# ProPrj_OpenTCUV4_2026-04-02.net
KiCad netlist of a schematic drawn in EasyEDA Pro
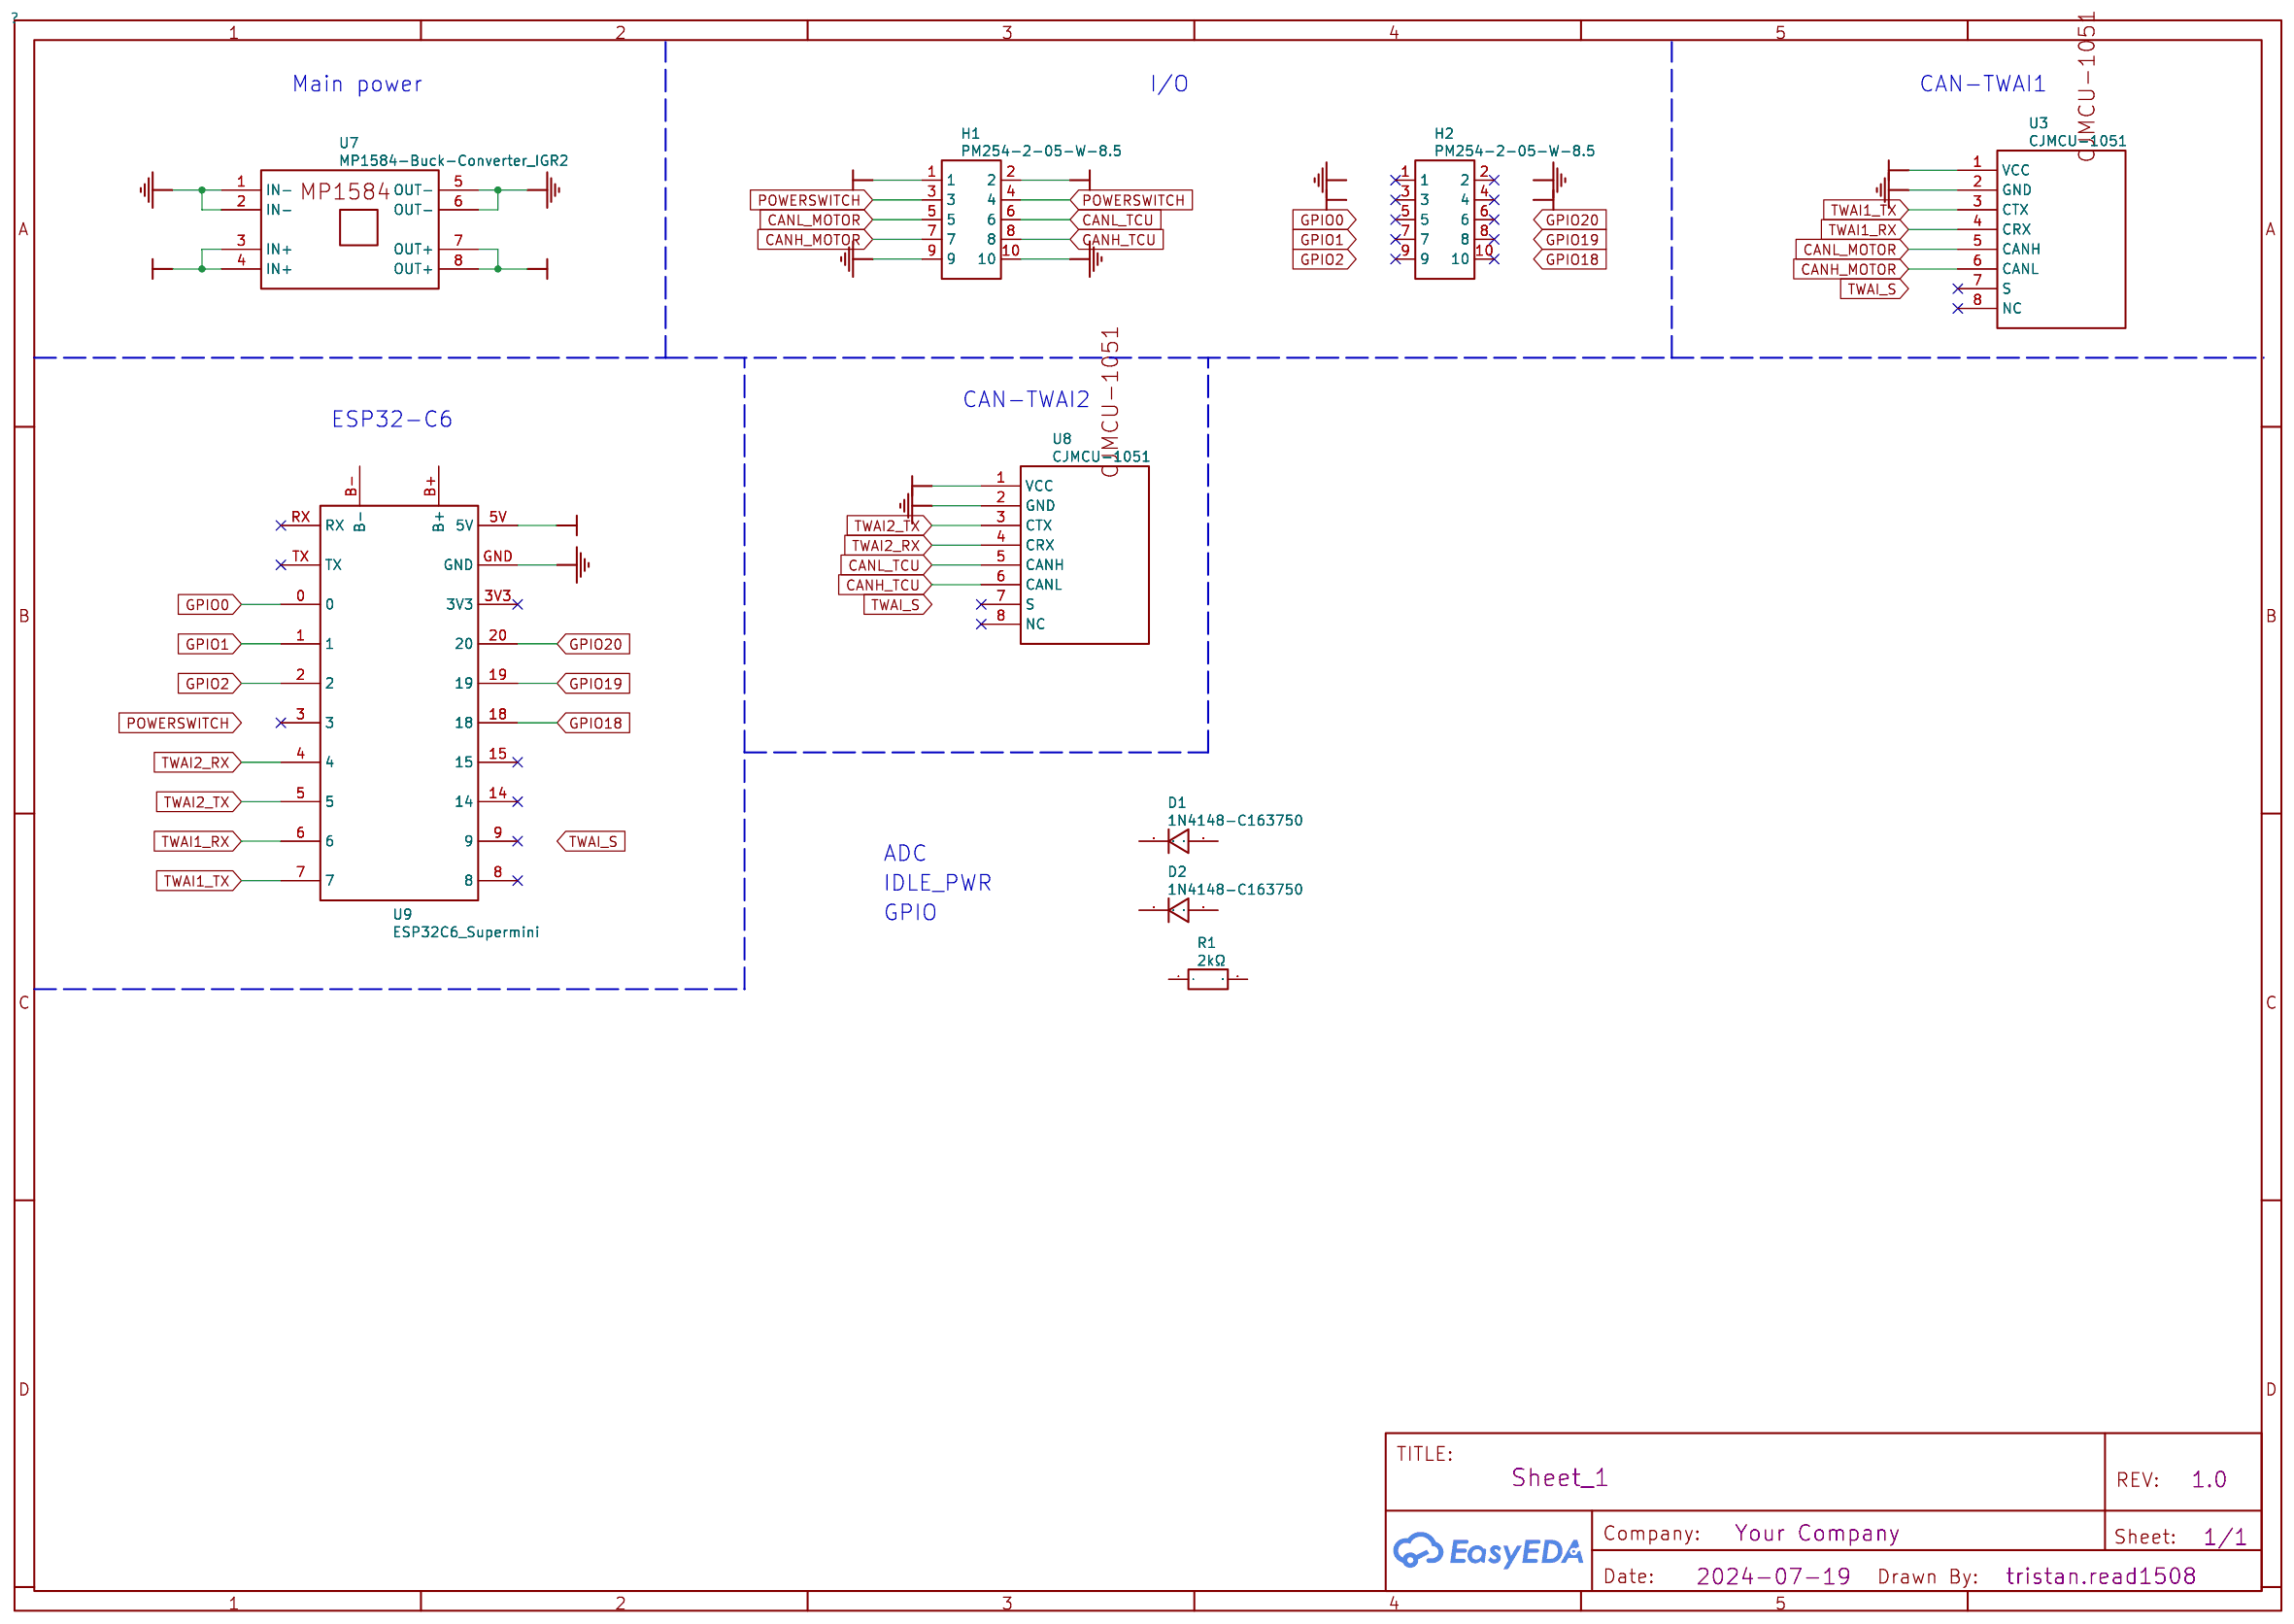
[diagram p0: schematic sheet]

(export (version "E")
  (design (tool "Eeschema 10.0.6"))
  (components
    (comp (ref "D1")
      (value "1N4148-C163750")
      (footprint "easyedapro:DO-35_BD2.0-L4.2-P8.20-D0.5-RD")
      (fields
        (field (name "Manufacturer Part") "1N4148")
        (field (name "Manufacturer") "FMS(美丽微)")
        (field (name "Contributor") "LCSC")
      )
      (libsource (lib "easyedapro") (part "1N4148-C163750"))
    )
    (comp (ref "D2")
      (value "1N4148-C163750")
      (footprint "easyedapro:DO-35_BD2.0-L4.2-P8.20-D0.5-RD")
      (fields
        (field (name "Manufacturer Part") "1N4148")
        (field (name "Manufacturer") "FMS(美丽微)")
        (field (name "Contributor") "LCSC")
      )
      (libsource (lib "easyedapro") (part "1N4148-C163750"))
    )
    (comp (ref "H1")
      (value "PM254-2-05-W-8.5")
      (footprint "easyedapro:HDR-TH_10P-P2.54-H-F-R2-C5-W8.5")
      (fields (field (name "Manufacturer") "HCTL(华灿天禄)") (field (name "Contributor") "LCSC"))
      (libsource (lib "easyedapro") (part "PM254-2-05-W-8.5"))
    )
    (comp (ref "H2")
      (value "PM254-2-05-W-8.5")
      (footprint "easyedapro:HDR-TH_10P-P2.54-H-F-R2-C5-W8.5")
      (fields (field (name "Manufacturer") "HCTL(华灿天禄)") (field (name "Contributor") "LCSC"))
      (libsource (lib "easyedapro") (part "PM254-2-05-W-8.5"))
    )
    (comp (ref "R1")
      (value "2kΩ")
      (footprint "easyedapro:RES-TH_BD2.4-L6.3-P10.30-D0.6")
      (fields
        (field (name "Manufacturer Part") "RN1/4W2KFT/BA1")
        (field (name "Manufacturer") "Tyohm(幸亚电阻)")
        (field (name "Contributor") "LCSC")
      )
      (libsource (lib "easyedapro") (part "2kΩ"))
    )
    (comp (ref "U3")
      (value "CJMCU-1051")
      (footprint "easyedapro:CJMCU-1051")
      (fields (field (name "Contributor") "ratedspg10"))
      (libsource (lib "easyedapro") (part "CJMCU-1051"))
    )
    (comp (ref "U7")
      (value "MP1584-Buck-Converter_IGR2")
      (footprint "easyedapro:MP1584EN-BUCK-CONVERTER")
      (fields (field (name "Manufacturer Part") "MP1584EN") (field (name "Contributor") "fazli wadood"))
      (libsource (lib "easyedapro") (part "MP1584-Buck-Converter_IGR2"))
    )
    (comp (ref "U8")
      (value "CJMCU-1051")
      (footprint "easyedapro:CJMCU-1051")
      (fields (field (name "Contributor") "ratedspg10"))
      (libsource (lib "easyedapro") (part "CJMCU-1051"))
    )
    (comp (ref "U9")
      (value "ESP32C6_Supermini")
      (footprint "easyedapro:ESP32-C6-SUPERMINI")
      (fields (field (name "Contributor") "Guest"))
      (libsource (lib "easyedapro") (part "ESP32C6_Supermini"))
    )
  )
  (nets
    (net (code "1") (name "+5V") (class "Default")
      (node (ref "U3") (pin "1") (pinfunction "VCC_1") (pintype "unspecified"))
      (node (ref "U7") (pin "7") (pinfunction "OUT+_7") (pintype "unspecified"))
      (node (ref "U7") (pin "8") (pinfunction "OUT+_8") (pintype "unspecified"))
      (node (ref "U8") (pin "1") (pinfunction "VCC_1") (pintype "unspecified"))
      (node (ref "U9") (pin "5V") (pinfunction "5V_5V") (pintype "unspecified"))
    )
    (net (code "2") (name "CANH_MOTOR") (class "Default")
      (node (ref "H1") (pin "7") (pinfunction "7_7") (pintype "unspecified"))
      (node (ref "U3") (pin "6") (pinfunction "CANL_6") (pintype "unspecified"))
    )
    (net (code "3") (name "CANH_TCU") (class "Default")
      (node (ref "H1") (pin "8") (pinfunction "8_8") (pintype "unspecified"))
      (node (ref "U8") (pin "6") (pinfunction "CANL_6") (pintype "unspecified"))
    )
    (net (code "4") (name "CANL_MOTOR") (class "Default")
      (node (ref "H1") (pin "5") (pinfunction "5_5") (pintype "unspecified"))
      (node (ref "U3") (pin "5") (pinfunction "CANH_5") (pintype "unspecified"))
    )
    (net (code "5") (name "CANL_TCU") (class "Default")
      (node (ref "H1") (pin "6") (pinfunction "6_6") (pintype "unspecified"))
      (node (ref "U8") (pin "5") (pinfunction "CANH_5") (pintype "unspecified"))
    )
    (net (code "6") (name "GND") (class "Default")
      (node (ref "H1") (pin "10") (pinfunction "10_10") (pintype "unspecified"))
      (node (ref "H1") (pin "9") (pinfunction "9_9") (pintype "unspecified"))
      (node (ref "U3") (pin "2") (pinfunction "GND_2") (pintype "unspecified"))
      (node (ref "U7") (pin "1") (pinfunction "IN-_1") (pintype "unspecified"))
      (node (ref "U7") (pin "2") (pinfunction "IN-_2") (pintype "unspecified"))
      (node (ref "U7") (pin "5") (pinfunction "OUT-_5") (pintype "unspecified"))
      (node (ref "U7") (pin "6") (pinfunction "OUT-_6") (pintype "unspecified"))
      (node (ref "U8") (pin "2") (pinfunction "GND_2") (pintype "unspecified"))
      (node (ref "U9") (pin "GND") (pinfunction "GND_GND") (pintype "unspecified"))
    )
    (net (code "7") (name "GPIO0") (class "Default")
      (node (ref "U9") (pin "0") (pinfunction "0_0") (pintype "bidirectional"))
    )
    (net (code "8") (name "GPIO1") (class "Default")
      (node (ref "U9") (pin "1") (pinfunction "1_1") (pintype "bidirectional"))
    )
    (net (code "9") (name "GPIO2") (class "Default")
      (node (ref "U9") (pin "2") (pinfunction "2_2") (pintype "bidirectional"))
    )
    (net (code "10") (name "GPIO18") (class "Default")
      (node (ref "U9") (pin "18") (pinfunction "18_18") (pintype "unspecified"))
    )
    (net (code "11") (name "GPIO19") (class "Default")
      (node (ref "U9") (pin "19") (pinfunction "19_19") (pintype "unspecified"))
    )
    (net (code "12") (name "GPIO20") (class "Default")
      (node (ref "U9") (pin "20") (pinfunction "20_20") (pintype "unspecified"))
    )
    (net (code "13") (name "POWERSWITCH") (class "Default")
      (node (ref "H1") (pin "3") (pinfunction "3_3") (pintype "unspecified"))
      (node (ref "H1") (pin "4") (pinfunction "4_4") (pintype "unspecified"))
    )
    (net (code "14") (name "TWAI1_RX") (class "Default")
      (node (ref "U3") (pin "4") (pinfunction "CRX_4") (pintype "unspecified"))
      (node (ref "U9") (pin "6") (pinfunction "6_6") (pintype "bidirectional"))
    )
    (net (code "15") (name "TWAI1_TX") (class "Default")
      (node (ref "U3") (pin "3") (pinfunction "CTX_3") (pintype "unspecified"))
      (node (ref "U9") (pin "7") (pinfunction "7_7") (pintype "bidirectional"))
    )
    (net (code "16") (name "TWAI2_RX") (class "Default")
      (node (ref "U8") (pin "4") (pinfunction "CRX_4") (pintype "unspecified"))
      (node (ref "U9") (pin "4") (pinfunction "4_4") (pintype "bidirectional"))
    )
    (net (code "17") (name "TWAI2_TX") (class "Default")
      (node (ref "U8") (pin "3") (pinfunction "CTX_3") (pintype "unspecified"))
      (node (ref "U9") (pin "5") (pinfunction "5_5") (pintype "bidirectional"))
    )
    (net (code "19") (name "VCC") (class "Default")
      (node (ref "H1") (pin "1") (pinfunction "1_1") (pintype "unspecified"))
      (node (ref "H1") (pin "2") (pinfunction "2_2") (pintype "unspecified"))
      (node (ref "U7") (pin "3") (pinfunction "IN+_3") (pintype "unspecified"))
      (node (ref "U7") (pin "4") (pinfunction "IN+_4") (pintype "unspecified"))
    )
    (net (code "20") (name "unconnected-(D1-Pad1)") (class "Default")
      (node (ref "D1") (pin "1") (pinfunction "1_1") (pintype "unspecified"))
    )
    (net (code "21") (name "unconnected-(D1-Pad2)") (class "Default")
      (node (ref "D1") (pin "2") (pinfunction "2_2") (pintype "unspecified"))
    )
    (net (code "22") (name "unconnected-(D2-Pad1)") (class "Default")
      (node (ref "D2") (pin "1") (pinfunction "1_1") (pintype "unspecified"))
    )
    (net (code "23") (name "unconnected-(D2-Pad2)") (class "Default")
      (node (ref "D2") (pin "2") (pinfunction "2_2") (pintype "unspecified"))
    )
    (net (code "24") (name "unconnected-(H2-Pad1)") (class "Default")
      (node (ref "H2") (pin "1") (pinfunction "1_1") (pintype "unspecified+no_connect"))
    )
    (net (code "25") (name "unconnected-(H2-Pad2)") (class "Default")
      (node (ref "H2") (pin "2") (pinfunction "2_2") (pintype "unspecified+no_connect"))
    )
    (net (code "26") (name "unconnected-(H2-Pad3)") (class "Default")
      (node (ref "H2") (pin "3") (pinfunction "3_3") (pintype "unspecified+no_connect"))
    )
    (net (code "27") (name "unconnected-(H2-Pad4)") (class "Default")
      (node (ref "H2") (pin "4") (pinfunction "4_4") (pintype "unspecified+no_connect"))
    )
    (net (code "28") (name "unconnected-(H2-Pad5)") (class "Default")
      (node (ref "H2") (pin "5") (pinfunction "5_5") (pintype "unspecified+no_connect"))
    )
    (net (code "29") (name "unconnected-(H2-Pad6)") (class "Default")
      (node (ref "H2") (pin "6") (pinfunction "6_6") (pintype "unspecified+no_connect"))
    )
    (net (code "30") (name "unconnected-(H2-Pad7)") (class "Default")
      (node (ref "H2") (pin "7") (pinfunction "7_7") (pintype "unspecified+no_connect"))
    )
    (net (code "31") (name "unconnected-(H2-Pad8)") (class "Default")
      (node (ref "H2") (pin "8") (pinfunction "8_8") (pintype "unspecified+no_connect"))
    )
    (net (code "32") (name "unconnected-(H2-Pad9)") (class "Default")
      (node (ref "H2") (pin "9") (pinfunction "9_9") (pintype "unspecified+no_connect"))
    )
    (net (code "33") (name "unconnected-(H2-Pad10)") (class "Default")
      (node (ref "H2") (pin "10") (pinfunction "10_10") (pintype "unspecified+no_connect"))
    )
    (net (code "34") (name "unconnected-(R1-Pad1)") (class "Default")
      (node (ref "R1") (pin "1") (pinfunction "1_1") (pintype "unspecified"))
    )
    (net (code "35") (name "unconnected-(R1-Pad2)") (class "Default")
      (node (ref "R1") (pin "2") (pinfunction "2_2") (pintype "unspecified"))
    )
    (net (code "36") (name "unconnected-(U3-NC-Pad8)") (class "Default")
      (node (ref "U3") (pin "8") (pinfunction "NC_8") (pintype "unspecified+no_connect"))
    )
    (net (code "37") (name "unconnected-(U3-S-Pad7)") (class "Default")
      (node (ref "U3") (pin "7") (pinfunction "S_7") (pintype "unspecified+no_connect"))
    )
    (net (code "38") (name "unconnected-(U8-NC-Pad8)") (class "Default")
      (node (ref "U8") (pin "8") (pinfunction "NC_8") (pintype "unspecified+no_connect"))
    )
    (net (code "39") (name "unconnected-(U8-S-Pad7)") (class "Default")
      (node (ref "U8") (pin "7") (pinfunction "S_7") (pintype "unspecified+no_connect"))
    )
    (net (code "40") (name "unconnected-(U9-Pad3)") (class "Default")
      (node (ref "U9") (pin "3") (pinfunction "3_3") (pintype "bidirectional+no_connect"))
    )
    (net (code "41") (name "unconnected-(U9-Pad3V3)") (class "Default")
      (node (ref "U9") (pin "3V3") (pinfunction "3V3_3V3") (pintype "unspecified+no_connect"))
    )
    (net (code "42") (name "unconnected-(U9-Pad8)") (class "Default")
      (node (ref "U9") (pin "8") (pinfunction "8_8") (pintype "unspecified+no_connect"))
    )
    (net (code "43") (name "unconnected-(U9-Pad9)") (class "Default")
      (node (ref "U9") (pin "9") (pinfunction "9_9") (pintype "unspecified+no_connect"))
    )
    (net (code "44") (name "unconnected-(U9-Pad14)") (class "Default")
      (node (ref "U9") (pin "14") (pinfunction "14_14") (pintype "unspecified+no_connect"))
    )
    (net (code "45") (name "unconnected-(U9-Pad15)") (class "Default")
      (node (ref "U9") (pin "15") (pinfunction "15_15") (pintype "unspecified+no_connect"))
    )
    (net (code "46") (name "unconnected-(U9-PadB+)") (class "Default")
      (node (ref "U9") (pin "B+") (pinfunction "B+_B+") (pintype "unspecified"))
    )
    (net (code "47") (name "unconnected-(U9-PadB-)") (class "Default")
      (node (ref "U9") (pin "B-") (pinfunction "B-_B-") (pintype "unspecified"))
    )
    (net (code "48") (name "unconnected-(U9-PadRX)") (class "Default")
      (node (ref "U9") (pin "RX") (pinfunction "RX_RX") (pintype "unspecified+no_connect"))
    )
    (net (code "49") (name "unconnected-(U9-PadTX)") (class "Default")
      (node (ref "U9") (pin "TX") (pinfunction "TX_TX") (pintype "unspecified+no_connect"))
    )
  )
)
